# Sheet3.net
KiCad netlist of a schematic drawn in Altium Designer
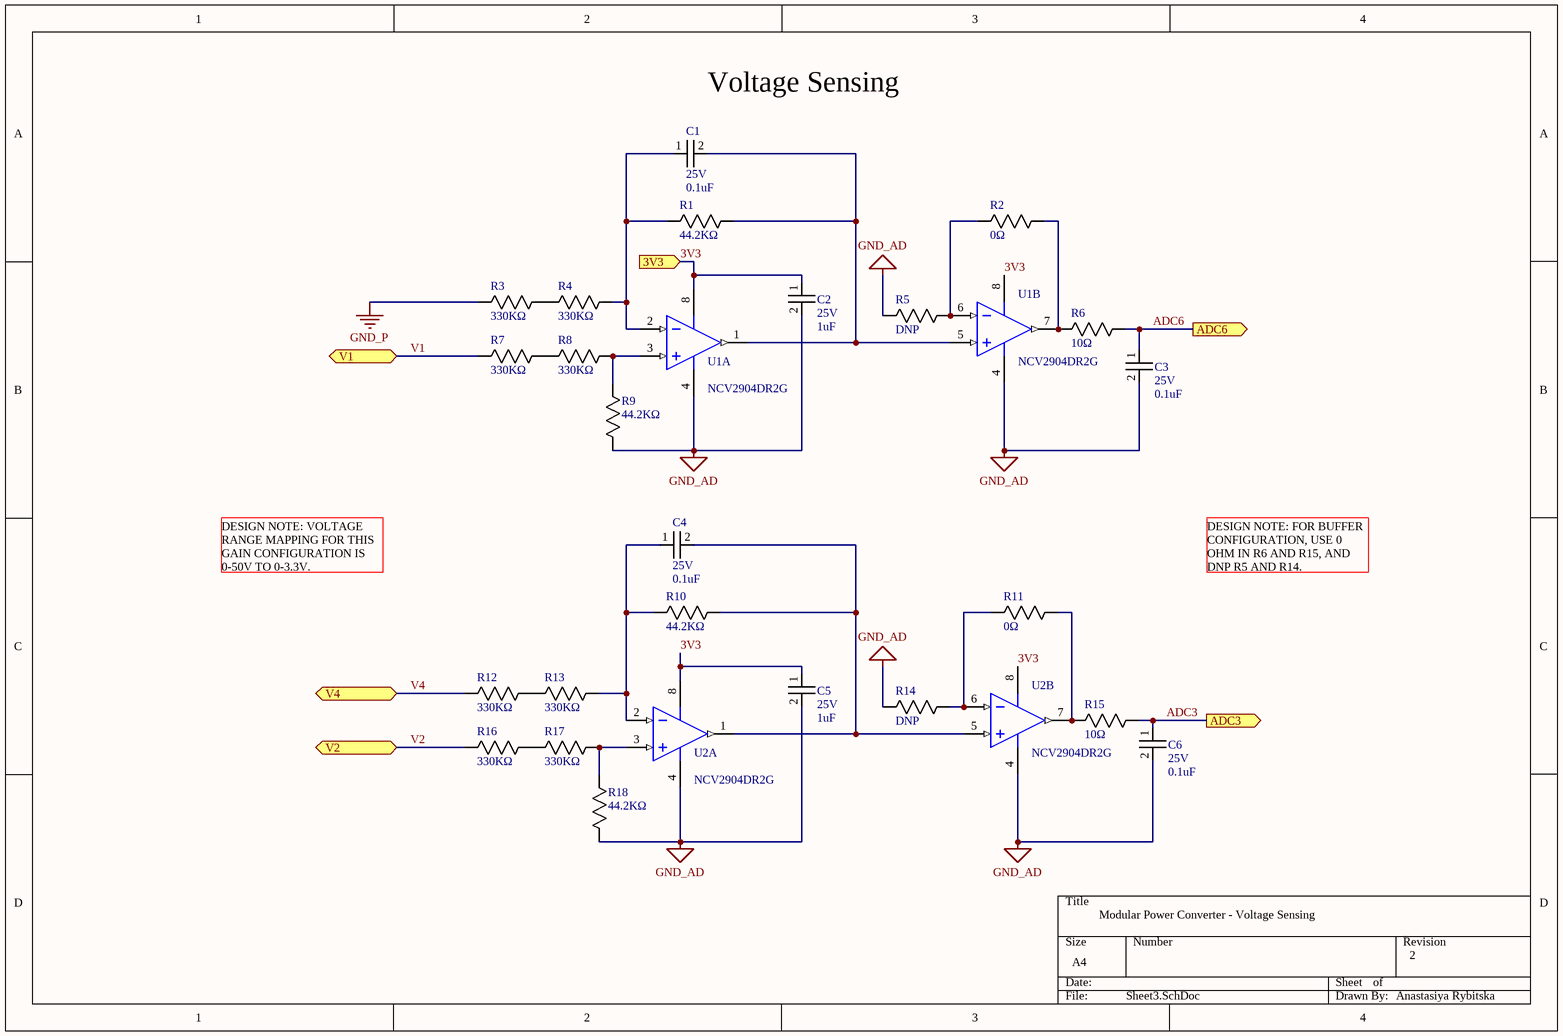
[diagram p0: Sheet3.SchDoc]

(export (version "E")
  (design (tool "Eeschema 10.0.6"))
  (components
    (comp (ref "C1")
      (value "CC0603MRX7R8BB104")
      (footprint "0603")
      (description "CAP CER 0.1UF 25V X7R 0603")
      (fields (field (name "VOLTAGE RATING") "25V") (field (name "CAPACITANCE") "0.1uF"))
      (libsource (lib "Schlib1") (part "CC0603MRX7R8BB104"))
    )
    (comp (ref "C2")
      (value "CL10B105KA8NFNC")
      (footprint "0603")
      (description "Cap Ceramic 1uF 25V X7R ±10% Pad SMD 0603 +125°C T/R")
      (fields (field (name "VOLTAGE RATING") "25V") (field (name "CAPACITANCE") "1uF"))
      (libsource (lib "Schlib1") (part "CL10B105KA8NFNC"))
    )
    (comp (ref "C3")
      (value "CC0603MRX7R8BB104")
      (footprint "0603")
      (description "CAP CER 0.1UF 25V X7R 0603")
      (fields (field (name "VOLTAGE RATING") "25V") (field (name "CAPACITANCE") "0.1uF"))
      (libsource (lib "Schlib1") (part "CC0603MRX7R8BB104"))
    )
    (comp (ref "C4")
      (value "CC0603MRX7R8BB104")
      (footprint "0603")
      (description "CAP CER 0.1UF 25V X7R 0603")
      (fields (field (name "VOLTAGE RATING") "25V") (field (name "CAPACITANCE") "0.1uF"))
      (libsource (lib "Schlib1") (part "CC0603MRX7R8BB104"))
    )
    (comp (ref "C5")
      (value "CL10B105KA8NFNC")
      (footprint "0603")
      (description "Cap Ceramic 1uF 25V X7R ±10% Pad SMD 0603 +125°C T/R")
      (fields (field (name "VOLTAGE RATING") "25V") (field (name "CAPACITANCE") "1uF"))
      (libsource (lib "Schlib1") (part "CL10B105KA8NFNC"))
    )
    (comp (ref "C6")
      (value "CC0603MRX7R8BB104")
      (footprint "0603")
      (description "CAP CER 0.1UF 25V X7R 0603")
      (fields (field (name "VOLTAGE RATING") "25V") (field (name "CAPACITANCE") "0.1uF"))
      (libsource (lib "Schlib1") (part "CC0603MRX7R8BB104"))
    )
    (comp (ref "R1")
      (value "RT0603FRE0744K2L")
      (footprint "0603")
      (description "RES SMD 44.2K OHM 1% 1/10W 0603")
      (fields (field (name "RESISTANCE") "44.2KΩ"))
      (libsource (lib "Schlib1") (part "RT0603FRE0744K2L"))
    )
    (comp (ref "R2")
      (value "AC0603FR-070RL")
      (footprint "0603")
      (description "RES SMD 0 OHM JUMPER 1/10W 0603")
      (fields (field (name "RESISTANCE") "0Ω"))
      (libsource (lib "Schlib1") (part "AC0603FR-070RL"))
    )
    (comp (ref "R3")
      (value "ERJ3EKF3303V")
      (footprint "0603")
      (fields (field (name "RESISTANCE") "330KΩ"))
      (libsource (lib "Schlib1") (part "ERJ3EKF3303V"))
    )
    (comp (ref "R4")
      (value "ERJ3EKF3303V")
      (footprint "0603")
      (fields (field (name "RESISTANCE") "330KΩ"))
      (libsource (lib "Schlib1") (part "ERJ3EKF3303V"))
    )
    (comp (ref "R5")
      (value "AC0603FR-070RL")
      (footprint "0603")
      (description "RES SMD 0 OHM JUMPER 1/10W 0603")
      (fields (field (name "RESISTANCE") "DNP"))
      (libsource (lib "Schlib1") (part "AC0603FR-070RL"))
    )
    (comp (ref "R6")
      (value "RMCF0603JT10R0")
      (footprint "0603")
      (description "RES 10 OHM 5% 1/10W 0603")
      (fields (field (name "RESISTANCE") "10Ω"))
      (libsource (lib "Schlib1") (part "RMCF0603JT10R0"))
    )
    (comp (ref "R7")
      (value "ERJ3EKF3303V")
      (footprint "0603")
      (fields (field (name "RESISTANCE") "330KΩ"))
      (libsource (lib "Schlib1") (part "ERJ3EKF3303V"))
    )
    (comp (ref "R8")
      (value "ERJ3EKF3303V")
      (footprint "0603")
      (fields (field (name "RESISTANCE") "330KΩ"))
      (libsource (lib "Schlib1") (part "ERJ3EKF3303V"))
    )
    (comp (ref "R9")
      (value "RT0603FRE0744K2L")
      (footprint "0603")
      (description "RES SMD 44.2K OHM 1% 1/10W 0603")
      (fields (field (name "RESISTANCE") "44.2KΩ"))
      (libsource (lib "Schlib1") (part "RT0603FRE0744K2L"))
    )
    (comp (ref "R10")
      (value "RT0603FRE0744K2L")
      (footprint "0603")
      (description "RES SMD 44.2K OHM 1% 1/10W 0603")
      (fields (field (name "RESISTANCE") "44.2KΩ"))
      (libsource (lib "Schlib1") (part "RT0603FRE0744K2L"))
    )
    (comp (ref "R11")
      (value "AC0603FR-070RL")
      (footprint "0603")
      (description "RES SMD 0 OHM JUMPER 1/10W 0603")
      (fields (field (name "RESISTANCE") "0Ω"))
      (libsource (lib "Schlib1") (part "AC0603FR-070RL"))
    )
    (comp (ref "R12")
      (value "ERJ3EKF3303V")
      (footprint "0603")
      (fields (field (name "RESISTANCE") "330KΩ"))
      (libsource (lib "Schlib1") (part "ERJ3EKF3303V"))
    )
    (comp (ref "R13")
      (value "ERJ3EKF3303V")
      (footprint "0603")
      (fields (field (name "RESISTANCE") "330KΩ"))
      (libsource (lib "Schlib1") (part "ERJ3EKF3303V"))
    )
    (comp (ref "R14")
      (value "AC0603FR-070RL")
      (footprint "0603")
      (description "RES SMD 0 OHM JUMPER 1/10W 0603")
      (fields (field (name "RESISTANCE") "DNP"))
      (libsource (lib "Schlib1") (part "AC0603FR-070RL"))
    )
    (comp (ref "R15")
      (value "RMCF0603JT10R0")
      (footprint "0603")
      (description "RES 10 OHM 5% 1/10W 0603")
      (fields (field (name "RESISTANCE") "10Ω"))
      (libsource (lib "Schlib1") (part "RMCF0603JT10R0"))
    )
    (comp (ref "R16")
      (value "ERJ3EKF3303V")
      (footprint "0603")
      (fields (field (name "RESISTANCE") "330KΩ"))
      (libsource (lib "Schlib1") (part "ERJ3EKF3303V"))
    )
    (comp (ref "R17")
      (value "ERJ3EKF3303V")
      (footprint "0603")
      (fields (field (name "RESISTANCE") "330KΩ"))
      (libsource (lib "Schlib1") (part "ERJ3EKF3303V"))
    )
    (comp (ref "R18")
      (value "RT0603FRE0744K2L")
      (footprint "0603")
      (description "RES SMD 44.2K OHM 1% 1/10W 0603")
      (fields (field (name "RESISTANCE") "44.2KΩ"))
      (libsource (lib "Schlib1") (part "RT0603FRE0744K2L"))
    )
    (comp (ref "U1")
      (value "NCV2904DR2G")
      (footprint "ONSC-SOIC-8-751-07_V")
      (fields (field (name "MANUFACTURER") "On Semiconductor"))
      (libsource (lib "Altium Content Vault") (part "ONSC-LM358_NCV2904-8"))
    )
    (comp (ref "U2")
      (value "NCV2904DR2G")
      (footprint "ONSC-SOIC-8-751-07_V")
      (fields (field (name "MANUFACTURER") "On Semiconductor"))
      (libsource (lib "Altium Content Vault") (part "ONSC-LM358_NCV2904-8"))
    )
  )
  (nets
    (net (code "1") (name "/3V3") (class "Default")
      (node (ref "C2") (pin "1") (pinfunction "1_1") (pintype "passive"))
      (node (ref "C5") (pin "1") (pinfunction "1_1") (pintype "passive"))
      (node (ref "U1") (pin "8") (pinfunction "VCC_8") (pintype "passive"))
      (node (ref "U2") (pin "8") (pinfunction "VCC_8") (pintype "passive"))
    )
    (net (code "2") (name "/ADC3") (class "Default")
      (node (ref "C6") (pin "1") (pinfunction "1_1") (pintype "passive"))
      (node (ref "R15") (pin "2") (pinfunction "2_2") (pintype "passive"))
    )
    (net (code "3") (name "/ADC6") (class "Default")
      (node (ref "C3") (pin "1") (pinfunction "1_1") (pintype "passive"))
      (node (ref "R6") (pin "2") (pinfunction "2_2") (pintype "passive"))
    )
    (net (code "4") (name "/V1") (class "Default")
      (node (ref "R7") (pin "1") (pinfunction "1_1") (pintype "passive"))
    )
    (net (code "5") (name "/V2") (class "Default")
      (node (ref "R16") (pin "1") (pinfunction "1_1") (pintype "passive"))
    )
    (net (code "6") (name "/V4") (class "Default")
      (node (ref "R12") (pin "1") (pinfunction "1_1") (pintype "passive"))
    )
    (net (code "7") (name "GND_AD") (class "Default")
      (node (ref "C2") (pin "2") (pinfunction "2_2") (pintype "passive"))
      (node (ref "C3") (pin "2") (pinfunction "2_2") (pintype "passive"))
      (node (ref "C5") (pin "2") (pinfunction "2_2") (pintype "passive"))
      (node (ref "C6") (pin "2") (pinfunction "2_2") (pintype "passive"))
      (node (ref "R14") (pin "1") (pinfunction "1_1") (pintype "passive"))
      (node (ref "R18") (pin "1") (pinfunction "1_1") (pintype "passive"))
      (node (ref "R5") (pin "1") (pinfunction "1_1") (pintype "passive"))
      (node (ref "R9") (pin "1") (pinfunction "1_1") (pintype "passive"))
      (node (ref "U1") (pin "4") (pinfunction "VEE/GND_4") (pintype "power_in"))
      (node (ref "U2") (pin "4") (pinfunction "VEE/GND_4") (pintype "power_in"))
    )
    (net (code "8") (name "GND_P") (class "Default")
      (node (ref "R3") (pin "1") (pinfunction "1_1") (pintype "passive"))
    )
    (net (code "9") (name "Net-(R3-Pad2)") (class "Default")
      (node (ref "R3") (pin "2") (pinfunction "2_2") (pintype "passive"))
      (node (ref "R4") (pin "1") (pinfunction "1_1") (pintype "passive"))
    )
    (net (code "10") (name "Net-(R7-Pad2)") (class "Default")
      (node (ref "R7") (pin "2") (pinfunction "2_2") (pintype "passive"))
      (node (ref "R8") (pin "1") (pinfunction "1_1") (pintype "passive"))
    )
    (net (code "11") (name "Net-(R12-Pad2)") (class "Default")
      (node (ref "R12") (pin "2") (pinfunction "2_2") (pintype "passive"))
      (node (ref "R13") (pin "1") (pinfunction "1_1") (pintype "passive"))
    )
    (net (code "12") (name "Net-(R16-Pad2)") (class "Default")
      (node (ref "R16") (pin "2") (pinfunction "2_2") (pintype "passive"))
      (node (ref "R17") (pin "1") (pinfunction "1_1") (pintype "passive"))
    )
    (net (code "13") (name "Net-(U1A-INA+)") (class "Default")
      (node (ref "R8") (pin "2") (pinfunction "2_2") (pintype "passive"))
      (node (ref "R9") (pin "2") (pinfunction "2_2") (pintype "passive"))
      (node (ref "U1") (pin "3") (pinfunction "INA+_3") (pintype "input"))
    )
    (net (code "14") (name "Net-(U1A-INA-)") (class "Default")
      (node (ref "C1") (pin "1") (pinfunction "1_1") (pintype "passive"))
      (node (ref "R1") (pin "1") (pinfunction "1_1") (pintype "passive"))
      (node (ref "R4") (pin "2") (pinfunction "2_2") (pintype "passive"))
      (node (ref "U1") (pin "2") (pinfunction "INA-_2") (pintype "input"))
    )
    (net (code "15") (name "Net-(U1A-OUTA)") (class "Default")
      (node (ref "C1") (pin "2") (pinfunction "2_2") (pintype "passive"))
      (node (ref "R1") (pin "2") (pinfunction "2_2") (pintype "passive"))
      (node (ref "U1") (pin "1") (pinfunction "OUTA_1") (pintype "output"))
      (node (ref "U1") (pin "5") (pinfunction "INB+_5") (pintype "input"))
    )
    (net (code "16") (name "Net-(U1B-INB-)") (class "Default")
      (node (ref "R2") (pin "1") (pinfunction "1_1") (pintype "passive"))
      (node (ref "R5") (pin "2") (pinfunction "2_2") (pintype "passive"))
      (node (ref "U1") (pin "6") (pinfunction "INB-_6") (pintype "input"))
    )
    (net (code "17") (name "Net-(U1B-OUTB)") (class "Default")
      (node (ref "R2") (pin "2") (pinfunction "2_2") (pintype "passive"))
      (node (ref "R6") (pin "1") (pinfunction "1_1") (pintype "passive"))
      (node (ref "U1") (pin "7") (pinfunction "OUTB_7") (pintype "output"))
    )
    (net (code "18") (name "Net-(U2A-INA+)") (class "Default")
      (node (ref "R17") (pin "2") (pinfunction "2_2") (pintype "passive"))
      (node (ref "R18") (pin "2") (pinfunction "2_2") (pintype "passive"))
      (node (ref "U2") (pin "3") (pinfunction "INA+_3") (pintype "input"))
    )
    (net (code "19") (name "Net-(U2A-INA-)") (class "Default")
      (node (ref "C4") (pin "1") (pinfunction "1_1") (pintype "passive"))
      (node (ref "R10") (pin "1") (pinfunction "1_1") (pintype "passive"))
      (node (ref "R13") (pin "2") (pinfunction "2_2") (pintype "passive"))
      (node (ref "U2") (pin "2") (pinfunction "INA-_2") (pintype "input"))
    )
    (net (code "20") (name "Net-(U2A-OUTA)") (class "Default")
      (node (ref "C4") (pin "2") (pinfunction "2_2") (pintype "passive"))
      (node (ref "R10") (pin "2") (pinfunction "2_2") (pintype "passive"))
      (node (ref "U2") (pin "1") (pinfunction "OUTA_1") (pintype "output"))
      (node (ref "U2") (pin "5") (pinfunction "INB+_5") (pintype "input"))
    )
    (net (code "21") (name "Net-(U2B-INB-)") (class "Default")
      (node (ref "R11") (pin "1") (pinfunction "1_1") (pintype "passive"))
      (node (ref "R14") (pin "2") (pinfunction "2_2") (pintype "passive"))
      (node (ref "U2") (pin "6") (pinfunction "INB-_6") (pintype "input"))
    )
    (net (code "22") (name "Net-(U2B-OUTB)") (class "Default")
      (node (ref "R11") (pin "2") (pinfunction "2_2") (pintype "passive"))
      (node (ref "R15") (pin "1") (pinfunction "1_1") (pintype "passive"))
      (node (ref "U2") (pin "7") (pinfunction "OUTB_7") (pintype "output"))
    )
  )
)
